# 780-00012-P3_rev2_Sch_M2_Focus_Drive.net
KiCad netlist of a schematic drawn in Altium Designer
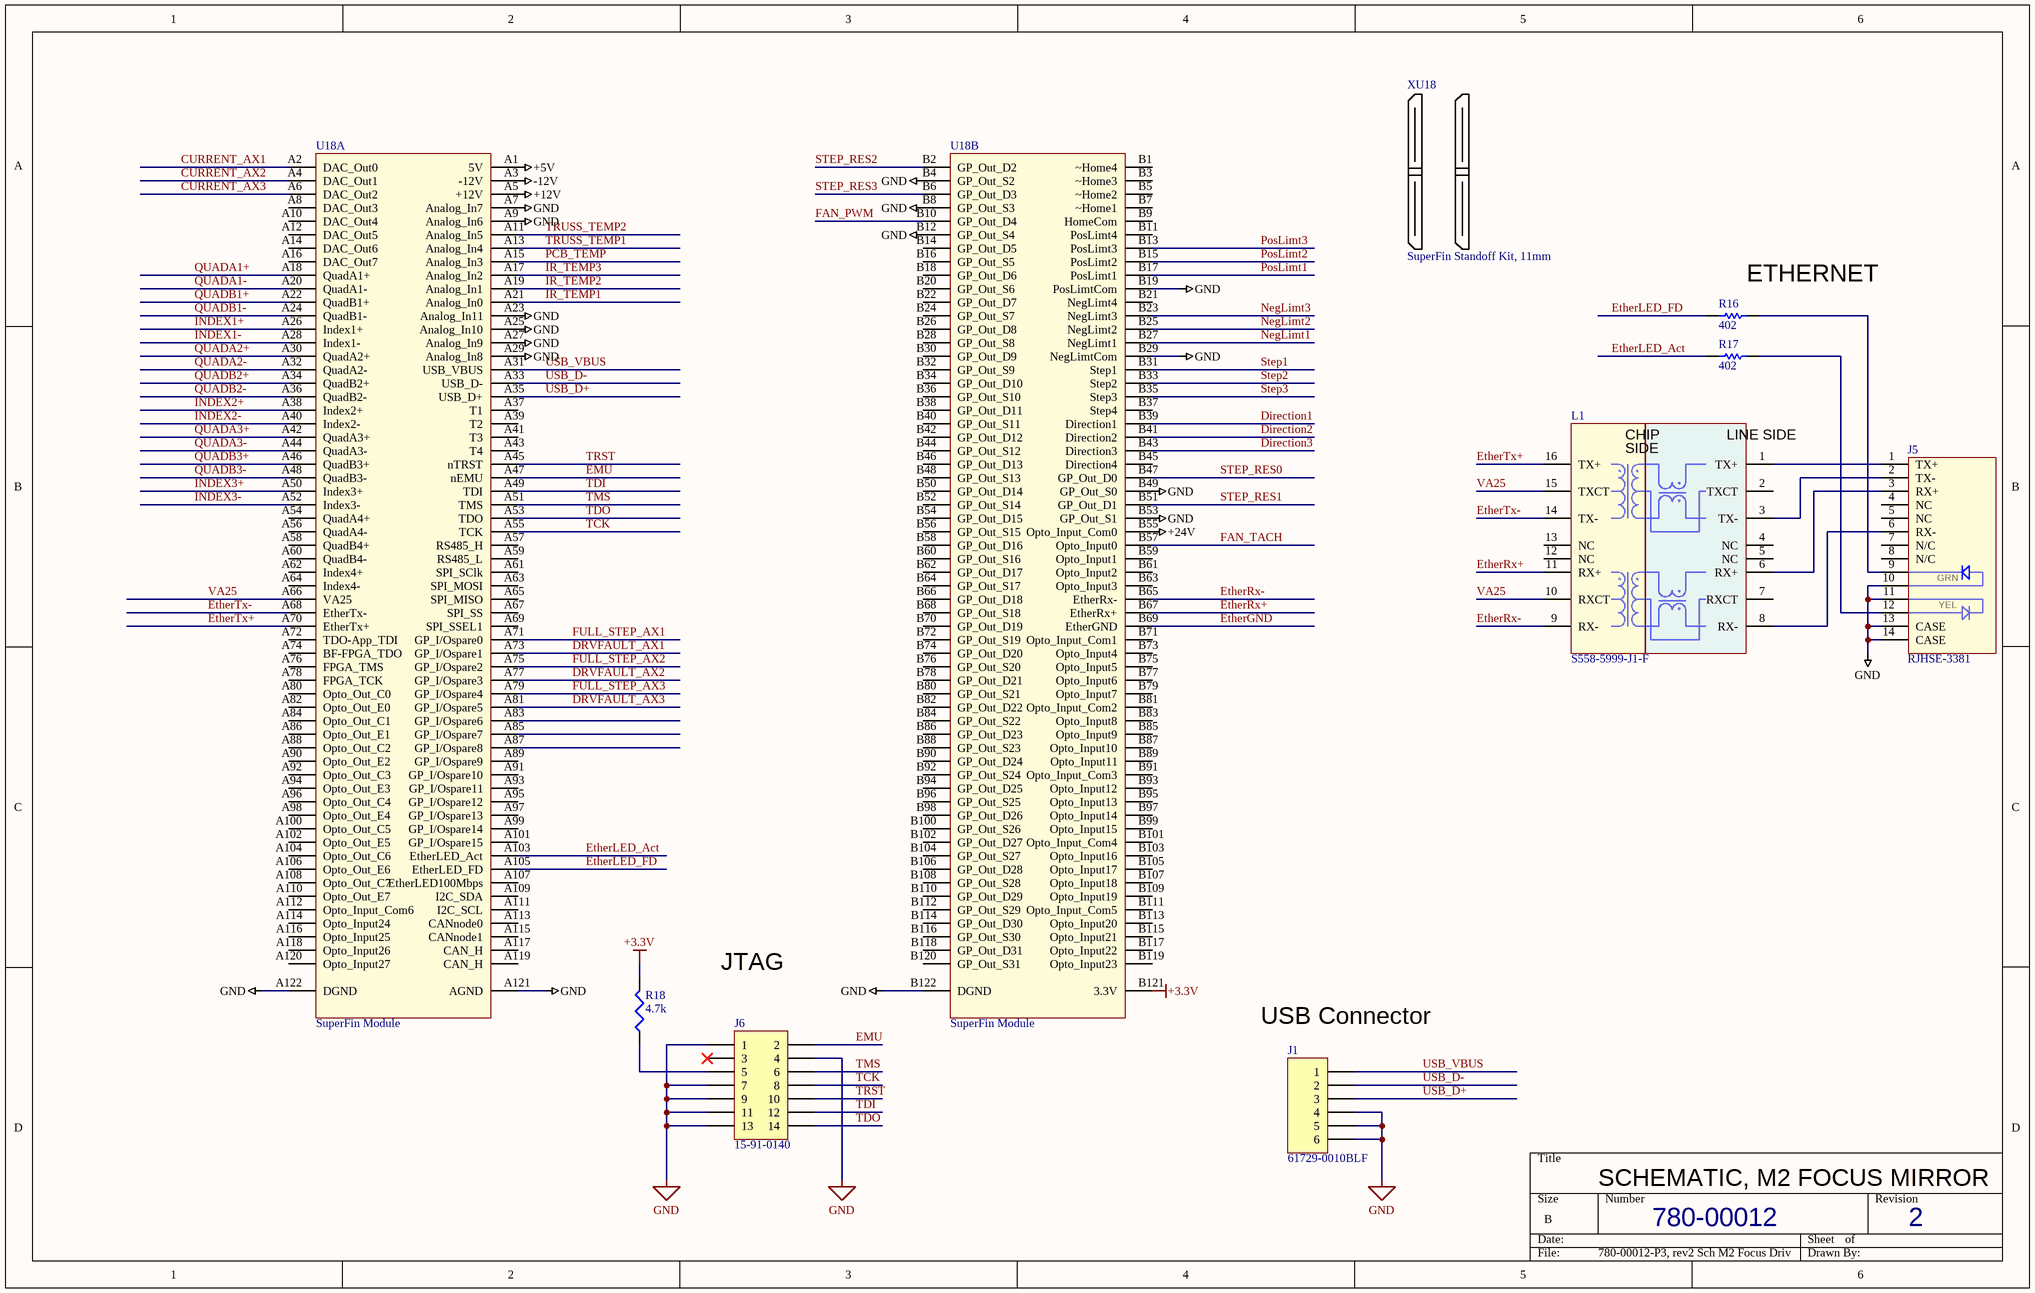
[diagram p0: 780-00012-P3, rev2 Sch M2 Focus Drive.SchDoc]

(export (version "E")
  (design (tool "Eeschema 10.0.6"))
  (components
    (comp (ref "J1")
      (value "61729-0010BLF")
      (footprint "USB Vertical PCB")
      (description "Header, 6-Pin")
      (fields (field (name "MANUFACTURER") "FCI"))
      (libsource (lib "Miscellaneous Connectors") (part "Header 6"))
    )
    (comp (ref "J5")
      (value "RJHSE-3381")
      (footprint "RJ45, VERT MOUNT, NO MAGNETICS")
      (description "Vertical PC mount, w/o magnetics")
      (libsource (lib "Richs Schematic Components") (part "CONN RJ-45 w/o magnetics"))
    )
    (comp (ref "J6")
      (value "15-91-0140")
      (footprint "HDR2X7")
      (description "Header, 7-Pin, Dual row")
      (fields (field (name "MANUFACTURER") "Molex/Waldom"))
      (libsource (lib "Miscellaneous Connectors") (part "Header 7X2"))
    )
    (comp (ref "L1")
      (value "S558-5999-J1-F")
      (footprint "10/100BT Magetics module")
      (description "10/100BT Magnetics Module")
      (libsource (lib "Richs Schematic Components") (part "Ethernet Magnetics module"))
    )
    (comp (ref "R16")
      (value "402")
      (footprint "SMD_0805")
      (description "Resistor 0805")
      (fields (field (name "MANUFACTURER") "Vishay/Dale") (field (name "Comment") "Res 0805"))
      (libsource (lib "Richs Schematic Components") (part "Res SMD"))
    )
    (comp (ref "R17")
      (value "402")
      (footprint "SMD_0805")
      (description "Resistor 0805")
      (fields (field (name "MANUFACTURER") "Vishay/Dale") (field (name "Comment") "Res 0805"))
      (libsource (lib "Richs Schematic Components") (part "Res SMD"))
    )
    (comp (ref "R18")
      (value "4.7k")
      (footprint "2012[0805]")
      (description "Resistor")
      (fields (field (name "MANUFACTURER") "Dale/Vishay"))
      (libsource (lib "Miscellaneous Devices") (part "Res3"))
    )
    (comp (ref "U18")
      (value "SuperFin Module")
      (footprint "SuperFin Footprint")
      (libsource (lib "Richs Schematic Components") (part "SuperFin Module"))
    )
    (comp (ref "XU18")
      (value "SuperFin Standoff Kit, 11mm")
      (libsource (lib "Richs Schematic Components") (part "SuperFin Standoff Kit, 11mm"))
    )
  )
  (nets
    (net (code "1") (name "+3.3V") (class "Default")
      (node (ref "R18") (pin "2") (pinfunction "2_2") (pintype "passive"))
      (node (ref "U18") (pin "B121") (pinfunction "3.3V_B121") (pintype "passive"))
    )
    (net (code "2") (name "+5V") (class "Default")
      (node (ref "U18") (pin "A1") (pinfunction "5V_A1") (pintype "passive"))
    )
    (net (code "3") (name "+12V") (class "Default")
      (node (ref "U18") (pin "A5") (pinfunction "+12V_A5") (pintype "passive"))
    )
    (net (code "4") (name "+24V") (class "Default")
      (node (ref "U18") (pin "B55") (pinfunction "Opto_Input_Com0_B55") (pintype "passive"))
    )
    (net (code "5") (name "-12V") (class "Default")
      (node (ref "U18") (pin "A3") (pinfunction "-12V_A3") (pintype "passive"))
    )
    (net (code "6") (name "/CURRENT_AX1") (class "Default")
      (node (ref "U18") (pin "A2") (pinfunction "DAC_Out0_A2") (pintype "passive"))
    )
    (net (code "7") (name "/CURRENT_AX2") (class "Default")
      (node (ref "U18") (pin "A4") (pinfunction "DAC_Out1_A4") (pintype "passive"))
    )
    (net (code "8") (name "/CURRENT_AX3") (class "Default")
      (node (ref "U18") (pin "A6") (pinfunction "DAC_Out2_A6") (pintype "passive"))
    )
    (net (code "9") (name "/DRVFAULT_AX1") (class "Default")
      (node (ref "U18") (pin "A73") (pinfunction "GP_I/Ospare1_A73") (pintype "passive"))
    )
    (net (code "10") (name "/DRVFAULT_AX2") (class "Default")
      (node (ref "U18") (pin "A77") (pinfunction "GP_I/Ospare3_A77") (pintype "passive"))
    )
    (net (code "11") (name "/DRVFAULT_AX3") (class "Default")
      (node (ref "U18") (pin "A81") (pinfunction "GP_I/Ospare5_A81") (pintype "passive"))
    )
    (net (code "12") (name "/Direction1") (class "Default")
      (node (ref "U18") (pin "B39") (pinfunction "Direction1_B39") (pintype "passive"))
    )
    (net (code "13") (name "/Direction2") (class "Default")
      (node (ref "U18") (pin "B41") (pinfunction "Direction2_B41") (pintype "passive"))
    )
    (net (code "14") (name "/Direction3") (class "Default")
      (node (ref "U18") (pin "B43") (pinfunction "Direction3_B43") (pintype "passive"))
    )
    (net (code "15") (name "/EMU") (class "Default")
      (node (ref "J6") (pin "2") (pinfunction "2_2") (pintype "passive"))
      (node (ref "U18") (pin "A47") (pinfunction "nEMU_A47") (pintype "passive"))
    )
    (net (code "16") (name "/EtherGND") (class "Default")
      (node (ref "U18") (pin "B69") (pinfunction "EtherGND_B69") (pintype "passive"))
    )
    (net (code "17") (name "/EtherLED_Act") (class "Default")
      (node (ref "R17") (pin "1") (pinfunction "1_1") (pintype "passive"))
      (node (ref "U18") (pin "A103") (pinfunction "EtherLED_Act_A103") (pintype "passive"))
    )
    (net (code "18") (name "/EtherLED_FD") (class "Default")
      (node (ref "R16") (pin "1") (pinfunction "1_1") (pintype "passive"))
      (node (ref "U18") (pin "A105") (pinfunction "EtherLED_FD_A105") (pintype "passive"))
    )
    (net (code "19") (name "/EtherRx+") (class "Default")
      (node (ref "L1") (pin "11") (pinfunction "RX+_11") (pintype "passive"))
      (node (ref "U18") (pin "B67") (pinfunction "EtherRx+_B67") (pintype "passive"))
    )
    (net (code "20") (name "/EtherRx-") (class "Default")
      (node (ref "L1") (pin "9") (pinfunction "RX-_9") (pintype "passive"))
      (node (ref "U18") (pin "B65") (pinfunction "EtherRx-_B65") (pintype "passive"))
    )
    (net (code "21") (name "/EtherTx+") (class "Default")
      (node (ref "L1") (pin "16") (pinfunction "TX+_16") (pintype "passive"))
      (node (ref "U18") (pin "A70") (pinfunction "EtherTx+_A70") (pintype "passive"))
    )
    (net (code "22") (name "/EtherTx-") (class "Default")
      (node (ref "L1") (pin "14") (pinfunction "TX-_14") (pintype "passive"))
      (node (ref "U18") (pin "A68") (pinfunction "EtherTx-_A68") (pintype "passive"))
    )
    (net (code "23") (name "/FAN_PWM") (class "Default")
      (node (ref "U18") (pin "B10") (pinfunction "GP_Out_D4_B10") (pintype "passive"))
    )
    (net (code "24") (name "/FAN_TACH") (class "Default")
      (node (ref "U18") (pin "B57") (pinfunction "Opto_Input0_B57") (pintype "passive"))
    )
    (net (code "25") (name "/FULL_STEP_AX1") (class "Default")
      (node (ref "U18") (pin "A71") (pinfunction "GP_I/Ospare0_A71") (pintype "passive"))
    )
    (net (code "26") (name "/FULL_STEP_AX2") (class "Default")
      (node (ref "U18") (pin "A75") (pinfunction "GP_I/Ospare2_A75") (pintype "passive"))
    )
    (net (code "27") (name "/FULL_STEP_AX3") (class "Default")
      (node (ref "U18") (pin "A79") (pinfunction "GP_I/Ospare4_A79") (pintype "passive"))
    )
    (net (code "28") (name "/INDEX1+") (class "Default")
      (node (ref "U18") (pin "A26") (pinfunction "Index1+_A26") (pintype "passive"))
    )
    (net (code "29") (name "/INDEX1-") (class "Default")
      (node (ref "U18") (pin "A28") (pinfunction "Index1-_A28") (pintype "passive"))
    )
    (net (code "30") (name "/INDEX2+") (class "Default")
      (node (ref "U18") (pin "A38") (pinfunction "Index2+_A38") (pintype "passive"))
    )
    (net (code "31") (name "/INDEX2-") (class "Default")
      (node (ref "U18") (pin "A40") (pinfunction "Index2-_A40") (pintype "passive"))
    )
    (net (code "32") (name "/INDEX3+") (class "Default")
      (node (ref "U18") (pin "A50") (pinfunction "Index3+_A50") (pintype "passive"))
    )
    (net (code "33") (name "/INDEX3-") (class "Default")
      (node (ref "U18") (pin "A52") (pinfunction "Index3-_A52") (pintype "passive"))
    )
    (net (code "34") (name "/IR_TEMP1") (class "Default")
      (node (ref "U18") (pin "A21") (pinfunction "Analog_In0_A21") (pintype "passive"))
    )
    (net (code "35") (name "/IR_TEMP2") (class "Default")
      (node (ref "U18") (pin "A19") (pinfunction "Analog_In1_A19") (pintype "passive"))
    )
    (net (code "36") (name "/IR_TEMP3") (class "Default")
      (node (ref "U18") (pin "A17") (pinfunction "Analog_In2_A17") (pintype "passive"))
    )
    (net (code "37") (name "/NegLimt1") (class "Default")
      (node (ref "U18") (pin "B27") (pinfunction "NegLimt1_B27") (pintype "passive"))
    )
    (net (code "38") (name "/NegLimt2") (class "Default")
      (node (ref "U18") (pin "B25") (pinfunction "NegLimt2_B25") (pintype "passive"))
    )
    (net (code "39") (name "/NegLimt3") (class "Default")
      (node (ref "U18") (pin "B23") (pinfunction "NegLimt3_B23") (pintype "passive"))
    )
    (net (code "40") (name "/PCB_TEMP") (class "Default")
      (node (ref "U18") (pin "A15") (pinfunction "Analog_In3_A15") (pintype "passive"))
    )
    (net (code "41") (name "/PosLimt1") (class "Default")
      (node (ref "U18") (pin "B17") (pinfunction "PosLimt1_B17") (pintype "passive"))
    )
    (net (code "42") (name "/PosLimt2") (class "Default")
      (node (ref "U18") (pin "B15") (pinfunction "PosLimt2_B15") (pintype "passive"))
    )
    (net (code "43") (name "/PosLimt3") (class "Default")
      (node (ref "U18") (pin "B13") (pinfunction "PosLimt3_B13") (pintype "passive"))
    )
    (net (code "44") (name "/QUADA1+") (class "Default")
      (node (ref "U18") (pin "A18") (pinfunction "QuadA1+_A18") (pintype "passive"))
    )
    (net (code "45") (name "/QUADA1-") (class "Default")
      (node (ref "U18") (pin "A20") (pinfunction "QuadA1-_A20") (pintype "passive"))
    )
    (net (code "46") (name "/QUADA2+") (class "Default")
      (node (ref "U18") (pin "A30") (pinfunction "QuadA2+_A30") (pintype "passive"))
    )
    (net (code "47") (name "/QUADA2-") (class "Default")
      (node (ref "U18") (pin "A32") (pinfunction "QuadA2-_A32") (pintype "passive"))
    )
    (net (code "48") (name "/QUADA3+") (class "Default")
      (node (ref "U18") (pin "A42") (pinfunction "QuadA3+_A42") (pintype "passive"))
    )
    (net (code "49") (name "/QUADA3-") (class "Default")
      (node (ref "U18") (pin "A44") (pinfunction "QuadA3-_A44") (pintype "passive"))
    )
    (net (code "50") (name "/QUADB1+") (class "Default")
      (node (ref "U18") (pin "A22") (pinfunction "QuadB1+_A22") (pintype "passive"))
    )
    (net (code "51") (name "/QUADB1-") (class "Default")
      (node (ref "U18") (pin "A24") (pinfunction "QuadB1-_A24") (pintype "passive"))
    )
    (net (code "52") (name "/QUADB2+") (class "Default")
      (node (ref "U18") (pin "A34") (pinfunction "QuadB2+_A34") (pintype "passive"))
    )
    (net (code "53") (name "/QUADB2-") (class "Default")
      (node (ref "U18") (pin "A36") (pinfunction "QuadB2-_A36") (pintype "passive"))
    )
    (net (code "54") (name "/QUADB3+") (class "Default")
      (node (ref "U18") (pin "A46") (pinfunction "QuadB3+_A46") (pintype "passive"))
    )
    (net (code "55") (name "/QUADB3-") (class "Default")
      (node (ref "U18") (pin "A48") (pinfunction "QuadB3-_A48") (pintype "passive"))
    )
    (net (code "56") (name "/STEP_RES0") (class "Default")
      (node (ref "U18") (pin "B47") (pinfunction "GP_Out_D0_B47") (pintype "passive"))
    )
    (net (code "57") (name "/STEP_RES1") (class "Default")
      (node (ref "U18") (pin "B51") (pinfunction "GP_Out_D1_B51") (pintype "passive"))
    )
    (net (code "58") (name "/STEP_RES2") (class "Default")
      (node (ref "U18") (pin "B2") (pinfunction "GP_Out_D2_B2") (pintype "passive"))
    )
    (net (code "59") (name "/STEP_RES3") (class "Default")
      (node (ref "U18") (pin "B6") (pinfunction "GP_Out_D3_B6") (pintype "passive"))
    )
    (net (code "60") (name "/Step1") (class "Default")
      (node (ref "U18") (pin "B31") (pinfunction "Step1_B31") (pintype "passive"))
    )
    (net (code "61") (name "/Step2") (class "Default")
      (node (ref "U18") (pin "B33") (pinfunction "Step2_B33") (pintype "passive"))
    )
    (net (code "62") (name "/Step3") (class "Default")
      (node (ref "U18") (pin "B35") (pinfunction "Step3_B35") (pintype "passive"))
    )
    (net (code "63") (name "/TCK") (class "Default")
      (node (ref "J6") (pin "8") (pinfunction "8_8") (pintype "passive"))
      (node (ref "U18") (pin "A55") (pinfunction "TCK_A55") (pintype "passive"))
    )
    (net (code "64") (name "/TDI") (class "Default")
      (node (ref "J6") (pin "12") (pinfunction "12_12") (pintype "passive"))
      (node (ref "U18") (pin "A49") (pinfunction "TDI_A49") (pintype "passive"))
    )
    (net (code "65") (name "/TDO") (class "Default")
      (node (ref "J6") (pin "14") (pinfunction "14_14") (pintype "passive"))
      (node (ref "U18") (pin "A53") (pinfunction "TDO_A53") (pintype "passive"))
    )
    (net (code "66") (name "/TMS") (class "Default")
      (node (ref "J6") (pin "6") (pinfunction "6_6") (pintype "passive"))
      (node (ref "U18") (pin "A51") (pinfunction "TMS_A51") (pintype "passive"))
    )
    (net (code "67") (name "/TRST") (class "Default")
      (node (ref "J6") (pin "10") (pinfunction "10_10") (pintype "passive"))
      (node (ref "U18") (pin "A45") (pinfunction "nTRST_A45") (pintype "passive"))
    )
    (net (code "68") (name "/TRUSS_TEMP1") (class "Default")
      (node (ref "U18") (pin "A13") (pinfunction "Analog_In4_A13") (pintype "passive"))
    )
    (net (code "69") (name "/TRUSS_TEMP2") (class "Default")
      (node (ref "U18") (pin "A11") (pinfunction "Analog_In5_A11") (pintype "passive"))
    )
    (net (code "70") (name "/USB_D+") (class "Default")
      (node (ref "J1") (pin "3") (pinfunction "3_3") (pintype "passive"))
      (node (ref "U18") (pin "A35") (pinfunction "USB_D+_A35") (pintype "passive"))
    )
    (net (code "71") (name "/USB_D-") (class "Default")
      (node (ref "J1") (pin "2") (pinfunction "2_2") (pintype "passive"))
      (node (ref "U18") (pin "A33") (pinfunction "USB_D-_A33") (pintype "passive"))
    )
    (net (code "72") (name "/USB_VBUS") (class "Default")
      (node (ref "J1") (pin "1") (pinfunction "1_1") (pintype "passive"))
      (node (ref "U18") (pin "A31") (pinfunction "USB_VBUS_A31") (pintype "passive"))
    )
    (net (code "73") (name "/VA25") (class "Default")
      (node (ref "L1") (pin "10") (pinfunction "RXCT_10") (pintype "passive"))
      (node (ref "L1") (pin "15") (pinfunction "TXCT_15") (pintype "passive"))
      (node (ref "U18") (pin "A66") (pinfunction "VA25_A66") (pintype "passive"))
    )
    (net (code "74") (name "GND") (class "Default")
      (node (ref "J1") (pin "4") (pinfunction "4_4") (pintype "passive"))
      (node (ref "J1") (pin "5") (pinfunction "5_5") (pintype "passive"))
      (node (ref "J1") (pin "6") (pinfunction "6_6") (pintype "passive"))
      (node (ref "J5") (pin "10") (pinfunction "GRN-Cathode_10") (pintype "passive"))
      (node (ref "J5") (pin "11") (pinfunction "YEL-Cathode_11") (pintype "passive"))
      (node (ref "J5") (pin "13") (pinfunction "CASE_13") (pintype "passive"))
      (node (ref "J5") (pin "14") (pinfunction "CASE_14") (pintype "passive"))
      (node (ref "J6") (pin "1") (pinfunction "1_1") (pintype "passive"))
      (node (ref "J6") (pin "11") (pinfunction "11_11") (pintype "passive"))
      (node (ref "J6") (pin "13") (pinfunction "13_13") (pintype "passive"))
      (node (ref "J6") (pin "4") (pinfunction "4_4") (pintype "passive"))
      (node (ref "J6") (pin "7") (pinfunction "7_7") (pintype "passive"))
      (node (ref "J6") (pin "9") (pinfunction "9_9") (pintype "passive"))
      (node (ref "U18") (pin "A121") (pinfunction "AGND_A121") (pintype "passive"))
      (node (ref "U18") (pin "A122") (pinfunction "DGND_A122") (pintype "passive"))
      (node (ref "U18") (pin "A23") (pinfunction "Analog_In11_A23") (pintype "passive"))
      (node (ref "U18") (pin "A25") (pinfunction "Analog_In10_A25") (pintype "passive"))
      (node (ref "U18") (pin "A27") (pinfunction "Analog_In9_A27") (pintype "passive"))
      (node (ref "U18") (pin "A29") (pinfunction "Analog_In8_A29") (pintype "passive"))
      (node (ref "U18") (pin "A7") (pinfunction "Analog_In7_A7") (pintype "passive"))
      (node (ref "U18") (pin "A9") (pinfunction "Analog_In6_A9") (pintype "passive"))
      (node (ref "U18") (pin "B12") (pinfunction "GP_Out_S4_B12") (pintype "passive"))
      (node (ref "U18") (pin "B122") (pinfunction "DGND_B122") (pintype "passive"))
      (node (ref "U18") (pin "B19") (pinfunction "PosLimtCom_B19") (pintype "passive"))
      (node (ref "U18") (pin "B29") (pinfunction "NegLimtCom_B29") (pintype "passive"))
      (node (ref "U18") (pin "B4") (pinfunction "GP_Out_S2_B4") (pintype "passive"))
      (node (ref "U18") (pin "B49") (pinfunction "GP_Out_S0_B49") (pintype "passive"))
      (node (ref "U18") (pin "B53") (pinfunction "GP_Out_S1_B53") (pintype "passive"))
      (node (ref "U18") (pin "B8") (pinfunction "GP_Out_S3_B8") (pintype "passive"))
    )
    (net (code "75") (name "Net-(J5-GRN-Anode)") (class "Default")
      (node (ref "J5") (pin "9") (pinfunction "GRN-Anode_9") (pintype "passive"))
      (node (ref "R16") (pin "2") (pinfunction "2_2") (pintype "passive"))
    )
    (net (code "76") (name "Net-(J5-RX+)") (class "Default")
      (node (ref "J5") (pin "3") (pinfunction "RX+_3") (pintype "passive"))
      (node (ref "L1") (pin "6") (pinfunction "RX+_6") (pintype "passive"))
    )
    (net (code "77") (name "Net-(J5-RX-)") (class "Default")
      (node (ref "J5") (pin "6") (pinfunction "RX-_6") (pintype "passive"))
      (node (ref "L1") (pin "8") (pinfunction "RX-_8") (pintype "passive"))
    )
    (net (code "78") (name "Net-(J5-TX+)") (class "Default")
      (node (ref "J5") (pin "1") (pinfunction "TX+_1") (pintype "passive"))
      (node (ref "L1") (pin "1") (pinfunction "TX+_1") (pintype "passive"))
    )
    (net (code "79") (name "Net-(J5-TX-)") (class "Default")
      (node (ref "J5") (pin "2") (pinfunction "TX-_2") (pintype "passive"))
      (node (ref "L1") (pin "3") (pinfunction "TX-_3") (pintype "passive"))
    )
    (net (code "80") (name "Net-(J5-YEL-Anode)") (class "Default")
      (node (ref "J5") (pin "12") (pinfunction "YEL-Anode_12") (pintype "passive"))
      (node (ref "R17") (pin "2") (pinfunction "2_2") (pintype "passive"))
    )
    (net (code "81") (name "Net-(J6-Pad5)") (class "Default")
      (node (ref "J6") (pin "5") (pinfunction "5_5") (pintype "passive"))
      (node (ref "R18") (pin "1") (pinfunction "1_1") (pintype "passive"))
    )
    (net (code "82") (name "unconnected-(J5-NC-Pad4)") (class "Default")
      (node (ref "J5") (pin "4") (pinfunction "NC_4") (pintype "passive"))
    )
    (net (code "83") (name "unconnected-(J5-NC-Pad5)") (class "Default")
      (node (ref "J5") (pin "5") (pinfunction "NC_5") (pintype "passive"))
    )
    (net (code "84") (name "unconnected-(J5-N{slash}C-Pad7)") (class "Default")
      (node (ref "J5") (pin "7") (pinfunction "N/C_7") (pintype "passive"))
    )
    (net (code "85") (name "unconnected-(J5-N{slash}C-Pad8)") (class "Default")
      (node (ref "J5") (pin "8") (pinfunction "N/C_8") (pintype "passive"))
    )
    (net (code "86") (name "unconnected-(J6-Pad3)") (class "Default")
      (node (ref "J6") (pin "3") (pinfunction "3_3") (pintype "passive+no_connect"))
    )
    (net (code "87") (name "unconnected-(L1-NC-Pad4)") (class "Default")
      (node (ref "L1") (pin "4") (pinfunction "NC_4") (pintype "passive"))
    )
    (net (code "88") (name "unconnected-(L1-NC-Pad5)") (class "Default")
      (node (ref "L1") (pin "5") (pinfunction "NC_5") (pintype "passive"))
    )
    (net (code "89") (name "unconnected-(L1-NC-Pad12)") (class "Default")
      (node (ref "L1") (pin "12") (pinfunction "NC_12") (pintype "passive"))
    )
    (net (code "90") (name "unconnected-(L1-NC-Pad13)") (class "Default")
      (node (ref "L1") (pin "13") (pinfunction "NC_13") (pintype "passive"))
    )
    (net (code "91") (name "unconnected-(L1-RXCT-Pad7)") (class "Default")
      (node (ref "L1") (pin "7") (pinfunction "RXCT_7") (pintype "passive"))
    )
    (net (code "92") (name "unconnected-(L1-TXCT-Pad2)") (class "Default")
      (node (ref "L1") (pin "2") (pinfunction "TXCT_2") (pintype "passive"))
    )
    (net (code "93") (name "unconnected-(U18A-BF-FPGA_TDO-PadA74)") (class "Default")
      (node (ref "U18") (pin "A74") (pinfunction "BF-FPGA_TDO_A74") (pintype "passive"))
    )
    (net (code "94") (name "unconnected-(U18A-CAN_H-PadA117)") (class "Default")
      (node (ref "U18") (pin "A117") (pinfunction "CAN_H_A117") (pintype "passive"))
    )
    (net (code "95") (name "unconnected-(U18A-CAN_H-PadA119)") (class "Default")
      (node (ref "U18") (pin "A119") (pinfunction "CAN_H_A119") (pintype "passive"))
    )
    (net (code "96") (name "unconnected-(U18A-CANnode0-PadA113)") (class "Default")
      (node (ref "U18") (pin "A113") (pinfunction "CANnode0_A113") (pintype "passive"))
    )
    (net (code "97") (name "unconnected-(U18A-CANnode1-PadA115)") (class "Default")
      (node (ref "U18") (pin "A115") (pinfunction "CANnode1_A115") (pintype "passive"))
    )
    (net (code "98") (name "unconnected-(U18A-DAC_Out3-PadA8)") (class "Default")
      (node (ref "U18") (pin "A8") (pinfunction "DAC_Out3_A8") (pintype "passive"))
    )
    (net (code "99") (name "unconnected-(U18A-DAC_Out4-PadA10)") (class "Default")
      (node (ref "U18") (pin "A10") (pinfunction "DAC_Out4_A10") (pintype "passive"))
    )
    (net (code "100") (name "unconnected-(U18A-DAC_Out5-PadA12)") (class "Default")
      (node (ref "U18") (pin "A12") (pinfunction "DAC_Out5_A12") (pintype "passive"))
    )
    (net (code "101") (name "unconnected-(U18A-DAC_Out6-PadA14)") (class "Default")
      (node (ref "U18") (pin "A14") (pinfunction "DAC_Out6_A14") (pintype "passive"))
    )
    (net (code "102") (name "unconnected-(U18A-DAC_Out7-PadA16)") (class "Default")
      (node (ref "U18") (pin "A16") (pinfunction "DAC_Out7_A16") (pintype "passive"))
    )
    (net (code "103") (name "unconnected-(U18A-EtherLED100Mbps-PadA107)") (class "Default")
      (node (ref "U18") (pin "A107") (pinfunction "EtherLED100Mbps_A107") (pintype "passive"))
    )
    (net (code "104") (name "unconnected-(U18A-FPGA_TCK-PadA78)") (class "Default")
      (node (ref "U18") (pin "A78") (pinfunction "FPGA_TCK_A78") (pintype "passive"))
    )
    (net (code "105") (name "unconnected-(U18A-FPGA_TMS-PadA76)") (class "Default")
      (node (ref "U18") (pin "A76") (pinfunction "FPGA_TMS_A76") (pintype "passive"))
    )
    (net (code "106") (name "unconnected-(U18A-GP_I{slash}Ospare6-PadA83)") (class "Default")
      (node (ref "U18") (pin "A83") (pinfunction "GP_I/Ospare6_A83") (pintype "passive"))
    )
    (net (code "107") (name "unconnected-(U18A-GP_I{slash}Ospare7-PadA85)") (class "Default")
      (node (ref "U18") (pin "A85") (pinfunction "GP_I/Ospare7_A85") (pintype "passive"))
    )
    (net (code "108") (name "unconnected-(U18A-GP_I{slash}Ospare8-PadA87)") (class "Default")
      (node (ref "U18") (pin "A87") (pinfunction "GP_I/Ospare8_A87") (pintype "passive"))
    )
    (net (code "109") (name "unconnected-(U18A-GP_I{slash}Ospare9-PadA89)") (class "Default")
      (node (ref "U18") (pin "A89") (pinfunction "GP_I/Ospare9_A89") (pintype "passive"))
    )
    (net (code "110") (name "unconnected-(U18A-GP_I{slash}Ospare10-PadA91)") (class "Default")
      (node (ref "U18") (pin "A91") (pinfunction "GP_I/Ospare10_A91") (pintype "passive"))
    )
    (net (code "111") (name "unconnected-(U18A-GP_I{slash}Ospare11-PadA93)") (class "Default")
      (node (ref "U18") (pin "A93") (pinfunction "GP_I/Ospare11_A93") (pintype "passive"))
    )
    (net (code "112") (name "unconnected-(U18A-GP_I{slash}Ospare12-PadA95)") (class "Default")
      (node (ref "U18") (pin "A95") (pinfunction "GP_I/Ospare12_A95") (pintype "passive"))
    )
    (net (code "113") (name "unconnected-(U18A-GP_I{slash}Ospare13-PadA97)") (class "Default")
      (node (ref "U18") (pin "A97") (pinfunction "GP_I/Ospare13_A97") (pintype "passive"))
    )
    (net (code "114") (name "unconnected-(U18A-GP_I{slash}Ospare14-PadA99)") (class "Default")
      (node (ref "U18") (pin "A99") (pinfunction "GP_I/Ospare14_A99") (pintype "passive"))
    )
    (net (code "115") (name "unconnected-(U18A-GP_I{slash}Ospare15-PadA101)") (class "Default")
      (node (ref "U18") (pin "A101") (pinfunction "GP_I/Ospare15_A101") (pintype "passive"))
    )
    (net (code "116") (name "unconnected-(U18A-I2C_SCL-PadA111)") (class "Default")
      (node (ref "U18") (pin "A111") (pinfunction "I2C_SCL_A111") (pintype "passive"))
    )
    (net (code "117") (name "unconnected-(U18A-I2C_SDA-PadA109)") (class "Default")
      (node (ref "U18") (pin "A109") (pinfunction "I2C_SDA_A109") (pintype "passive"))
    )
    (net (code "118") (name "unconnected-(U18A-Index4+-PadA62)") (class "Default")
      (node (ref "U18") (pin "A62") (pinfunction "Index4+_A62") (pintype "passive"))
    )
    (net (code "119") (name "unconnected-(U18A-Index4--PadA64)") (class "Default")
      (node (ref "U18") (pin "A64") (pinfunction "Index4-_A64") (pintype "passive"))
    )
    (net (code "120") (name "unconnected-(U18A-Opto_Input24-PadA114)") (class "Default")
      (node (ref "U18") (pin "A114") (pinfunction "Opto_Input24_A114") (pintype "passive"))
    )
    (net (code "121") (name "unconnected-(U18A-Opto_Input25-PadA116)") (class "Default")
      (node (ref "U18") (pin "A116") (pinfunction "Opto_Input25_A116") (pintype "passive"))
    )
    (net (code "122") (name "unconnected-(U18A-Opto_Input26-PadA118)") (class "Default")
      (node (ref "U18") (pin "A118") (pinfunction "Opto_Input26_A118") (pintype "passive"))
    )
    (net (code "123") (name "unconnected-(U18A-Opto_Input27-PadA120)") (class "Default")
      (node (ref "U18") (pin "A120") (pinfunction "Opto_Input27_A120") (pintype "passive"))
    )
    (net (code "124") (name "unconnected-(U18A-Opto_Input_Com6-PadA112)") (class "Default")
      (node (ref "U18") (pin "A112") (pinfunction "Opto_Input_Com6_A112") (pintype "passive"))
    )
    (net (code "125") (name "unconnected-(U18A-Opto_Out_C0-PadA80)") (class "Default")
      (node (ref "U18") (pin "A80") (pinfunction "Opto_Out_C0_A80") (pintype "passive"))
    )
    (net (code "126") (name "unconnected-(U18A-Opto_Out_C1-PadA84)") (class "Default")
      (node (ref "U18") (pin "A84") (pinfunction "Opto_Out_C1_A84") (pintype "passive"))
    )
    (net (code "127") (name "unconnected-(U18A-Opto_Out_C2-PadA88)") (class "Default")
      (node (ref "U18") (pin "A88") (pinfunction "Opto_Out_C2_A88") (pintype "passive"))
    )
    (net (code "128") (name "unconnected-(U18A-Opto_Out_C3-PadA92)") (class "Default")
      (node (ref "U18") (pin "A92") (pinfunction "Opto_Out_C3_A92") (pintype "passive"))
    )
    (net (code "129") (name "unconnected-(U18A-Opto_Out_C4-PadA96)") (class "Default")
      (node (ref "U18") (pin "A96") (pinfunction "Opto_Out_C4_A96") (pintype "passive"))
    )
    (net (code "130") (name "unconnected-(U18A-Opto_Out_C5-PadA100)") (class "Default")
      (node (ref "U18") (pin "A100") (pinfunction "Opto_Out_C5_A100") (pintype "passive"))
    )
    (net (code "131") (name "unconnected-(U18A-Opto_Out_C6-PadA104)") (class "Default")
      (node (ref "U18") (pin "A104") (pinfunction "Opto_Out_C6_A104") (pintype "passive"))
    )
    (net (code "132") (name "unconnected-(U18A-Opto_Out_C7-PadA108)") (class "Default")
      (node (ref "U18") (pin "A108") (pinfunction "Opto_Out_C7_A108") (pintype "passive"))
    )
    (net (code "133") (name "unconnected-(U18A-Opto_Out_E0-PadA82)") (class "Default")
      (node (ref "U18") (pin "A82") (pinfunction "Opto_Out_E0_A82") (pintype "passive"))
    )
    (net (code "134") (name "unconnected-(U18A-Opto_Out_E1-PadA86)") (class "Default")
      (node (ref "U18") (pin "A86") (pinfunction "Opto_Out_E1_A86") (pintype "passive"))
    )
    (net (code "135") (name "unconnected-(U18A-Opto_Out_E2-PadA90)") (class "Default")
      (node (ref "U18") (pin "A90") (pinfunction "Opto_Out_E2_A90") (pintype "passive"))
    )
    (net (code "136") (name "unconnected-(U18A-Opto_Out_E3-PadA94)") (class "Default")
      (node (ref "U18") (pin "A94") (pinfunction "Opto_Out_E3_A94") (pintype "passive"))
    )
    (net (code "137") (name "unconnected-(U18A-Opto_Out_E4-PadA98)") (class "Default")
      (node (ref "U18") (pin "A98") (pinfunction "Opto_Out_E4_A98") (pintype "passive"))
    )
    (net (code "138") (name "unconnected-(U18A-Opto_Out_E5-PadA102)") (class "Default")
      (node (ref "U18") (pin "A102") (pinfunction "Opto_Out_E5_A102") (pintype "passive"))
    )
    (net (code "139") (name "unconnected-(U18A-Opto_Out_E6-PadA106)") (class "Default")
      (node (ref "U18") (pin "A106") (pinfunction "Opto_Out_E6_A106") (pintype "passive"))
    )
    (net (code "140") (name "unconnected-(U18A-Opto_Out_E7-PadA110)") (class "Default")
      (node (ref "U18") (pin "A110") (pinfunction "Opto_Out_E7_A110") (pintype "passive"))
    )
    (net (code "141") (name "unconnected-(U18A-QuadA4+-PadA54)") (class "Default")
      (node (ref "U18") (pin "A54") (pinfunction "QuadA4+_A54") (pintype "passive"))
    )
    (net (code "142") (name "unconnected-(U18A-QuadA4--PadA56)") (class "Default")
      (node (ref "U18") (pin "A56") (pinfunction "QuadA4-_A56") (pintype "passive"))
    )
    (net (code "143") (name "unconnected-(U18A-QuadB4+-PadA58)") (class "Default")
      (node (ref "U18") (pin "A58") (pinfunction "QuadB4+_A58") (pintype "passive"))
    )
    (net (code "144") (name "unconnected-(U18A-QuadB4--PadA60)") (class "Default")
      (node (ref "U18") (pin "A60") (pinfunction "QuadB4-_A60") (pintype "passive"))
    )
    (net (code "145") (name "unconnected-(U18A-RS485_H-PadA57)") (class "Default")
      (node (ref "U18") (pin "A57") (pinfunction "RS485_H_A57") (pintype "passive"))
    )
    (net (code "146") (name "unconnected-(U18A-RS485_L-PadA59)") (class "Default")
      (node (ref "U18") (pin "A59") (pinfunction "RS485_L_A59") (pintype "passive"))
    )
    (net (code "147") (name "unconnected-(U18A-SPI_MISO-PadA65)") (class "Default")
      (node (ref "U18") (pin "A65") (pinfunction "SPI_MISO_A65") (pintype "passive"))
    )
    (net (code "148") (name "unconnected-(U18A-SPI_MOSI-PadA63)") (class "Default")
      (node (ref "U18") (pin "A63") (pinfunction "SPI_MOSI_A63") (pintype "passive"))
    )
    (net (code "149") (name "unconnected-(U18A-SPI_SClk-PadA61)") (class "Default")
      (node (ref "U18") (pin "A61") (pinfunction "SPI_SClk_A61") (pintype "passive"))
    )
    (net (code "150") (name "unconnected-(U18A-SPI_SS-PadA67)") (class "Default")
      (node (ref "U18") (pin "A67") (pinfunction "SPI_SS_A67") (pintype "passive"))
    )
    (net (code "151") (name "unconnected-(U18A-SPI_SSEL1-PadA69)") (class "Default")
      (node (ref "U18") (pin "A69") (pinfunction "SPI_SSEL1_A69") (pintype "passive"))
    )
    (net (code "152") (name "unconnected-(U18A-T1-PadA37)") (class "Default")
      (node (ref "U18") (pin "A37") (pinfunction "T1_A37") (pintype "passive"))
    )
    (net (code "153") (name "unconnected-(U18A-T2-PadA39)") (class "Default")
      (node (ref "U18") (pin "A39") (pinfunction "T2_A39") (pintype "passive"))
    )
    (net (code "154") (name "unconnected-(U18A-T3-PadA41)") (class "Default")
      (node (ref "U18") (pin "A41") (pinfunction "T3_A41") (pintype "passive"))
    )
    (net (code "155") (name "unconnected-(U18A-T4-PadA43)") (class "Default")
      (node (ref "U18") (pin "A43") (pinfunction "T4_A43") (pintype "passive"))
    )
    (net (code "156") (name "unconnected-(U18A-TDO-App_TDI-PadA72)") (class "Default")
      (node (ref "U18") (pin "A72") (pinfunction "TDO-App_TDI_A72") (pintype "passive"))
    )
    (net (code "157") (name "unconnected-(U18B-Direction4-PadB45)") (class "Default")
      (node (ref "U18") (pin "B45") (pinfunction "Direction4_B45") (pintype "passive"))
    )
    (net (code "158") (name "unconnected-(U18B-GP_Out_D5-PadB14)") (class "Default")
      (node (ref "U18") (pin "B14") (pinfunction "GP_Out_D5_B14") (pintype "passive"))
    )
    (net (code "159") (name "unconnected-(U18B-GP_Out_D6-PadB18)") (class "Default")
      (node (ref "U18") (pin "B18") (pinfunction "GP_Out_D6_B18") (pintype "passive"))
    )
    (net (code "160") (name "unconnected-(U18B-GP_Out_D7-PadB22)") (class "Default")
      (node (ref "U18") (pin "B22") (pinfunction "GP_Out_D7_B22") (pintype "passive"))
    )
    (net (code "161") (name "unconnected-(U18B-GP_Out_D8-PadB26)") (class "Default")
      (node (ref "U18") (pin "B26") (pinfunction "GP_Out_D8_B26") (pintype "passive"))
    )
    (net (code "162") (name "unconnected-(U18B-GP_Out_D9-PadB30)") (class "Default")
      (node (ref "U18") (pin "B30") (pinfunction "GP_Out_D9_B30") (pintype "passive"))
    )
    (net (code "163") (name "unconnected-(U18B-GP_Out_D10-PadB34)") (class "Default")
      (node (ref "U18") (pin "B34") (pinfunction "GP_Out_D10_B34") (pintype "passive"))
    )
    (net (code "164") (name "unconnected-(U18B-GP_Out_D11-PadB38)") (class "Default")
      (node (ref "U18") (pin "B38") (pinfunction "GP_Out_D11_B38") (pintype "passive"))
    )
    (net (code "165") (name "unconnected-(U18B-GP_Out_D12-PadB42)") (class "Default")
      (node (ref "U18") (pin "B42") (pinfunction "GP_Out_D12_B42") (pintype "passive"))
    )
    (net (code "166") (name "unconnected-(U18B-GP_Out_D13-PadB46)") (class "Default")
      (node (ref "U18") (pin "B46") (pinfunction "GP_Out_D13_B46") (pintype "passive"))
    )
    (net (code "167") (name "unconnected-(U18B-GP_Out_D14-PadB50)") (class "Default")
      (node (ref "U18") (pin "B50") (pinfunction "GP_Out_D14_B50") (pintype "passive"))
    )
    (net (code "168") (name "unconnected-(U18B-GP_Out_D15-PadB54)") (class "Default")
      (node (ref "U18") (pin "B54") (pinfunction "GP_Out_D15_B54") (pintype "passive"))
    )
    (net (code "169") (name "unconnected-(U18B-GP_Out_D16-PadB58)") (class "Default")
      (node (ref "U18") (pin "B58") (pinfunction "GP_Out_D16_B58") (pintype "passive"))
    )
    (net (code "170") (name "unconnected-(U18B-GP_Out_D17-PadB62)") (class "Default")
      (node (ref "U18") (pin "B62") (pinfunction "GP_Out_D17_B62") (pintype "passive"))
    )
    (net (code "171") (name "unconnected-(U18B-GP_Out_D18-PadB66)") (class "Default")
      (node (ref "U18") (pin "B66") (pinfunction "GP_Out_D18_B66") (pintype "passive"))
    )
    (net (code "172") (name "unconnected-(U18B-GP_Out_D19-PadB70)") (class "Default")
      (node (ref "U18") (pin "B70") (pinfunction "GP_Out_D19_B70") (pintype "passive"))
    )
    (net (code "173") (name "unconnected-(U18B-GP_Out_D20-PadB74)") (class "Default")
      (node (ref "U18") (pin "B74") (pinfunction "GP_Out_D20_B74") (pintype "passive"))
    )
    (net (code "174") (name "unconnected-(U18B-GP_Out_D21-PadB78)") (class "Default")
      (node (ref "U18") (pin "B78") (pinfunction "GP_Out_D21_B78") (pintype "passive"))
    )
    (net (code "175") (name "unconnected-(U18B-GP_Out_D22-PadB82)") (class "Default")
      (node (ref "U18") (pin "B82") (pinfunction "GP_Out_D22_B82") (pintype "passive"))
    )
    (net (code "176") (name "unconnected-(U18B-GP_Out_D23-PadB86)") (class "Default")
      (node (ref "U18") (pin "B86") (pinfunction "GP_Out_D23_B86") (pintype "passive"))
    )
    (net (code "177") (name "unconnected-(U18B-GP_Out_D24-PadB90)") (class "Default")
      (node (ref "U18") (pin "B90") (pinfunction "GP_Out_D24_B90") (pintype "passive"))
    )
    (net (code "178") (name "unconnected-(U18B-GP_Out_D25-PadB94)") (class "Default")
      (node (ref "U18") (pin "B94") (pinfunction "GP_Out_D25_B94") (pintype "passive"))
    )
    (net (code "179") (name "unconnected-(U18B-GP_Out_D26-PadB98)") (class "Default")
      (node (ref "U18") (pin "B98") (pinfunction "GP_Out_D26_B98") (pintype "passive"))
    )
    (net (code "180") (name "unconnected-(U18B-GP_Out_D27-PadB102)") (class "Default")
      (node (ref "U18") (pin "B102") (pinfunction "GP_Out_D27_B102") (pintype "passive"))
    )
    (net (code "181") (name "unconnected-(U18B-GP_Out_D28-PadB106)") (class "Default")
      (node (ref "U18") (pin "B106") (pinfunction "GP_Out_D28_B106") (pintype "passive"))
    )
    (net (code "182") (name "unconnected-(U18B-GP_Out_D29-PadB110)") (class "Default")
      (node (ref "U18") (pin "B110") (pinfunction "GP_Out_D29_B110") (pintype "passive"))
    )
    (net (code "183") (name "unconnected-(U18B-GP_Out_D30-PadB114)") (class "Default")
      (node (ref "U18") (pin "B114") (pinfunction "GP_Out_D30_B114") (pintype "passive"))
    )
    (net (code "184") (name "unconnected-(U18B-GP_Out_D31-PadB118)") (class "Default")
      (node (ref "U18") (pin "B118") (pinfunction "GP_Out_D31_B118") (pintype "passive"))
    )
    (net (code "185") (name "unconnected-(U18B-GP_Out_S5-PadB16)") (class "Default")
      (node (ref "U18") (pin "B16") (pinfunction "GP_Out_S5_B16") (pintype "passive"))
    )
    (net (code "186") (name "unconnected-(U18B-GP_Out_S6-PadB20)") (class "Default")
      (node (ref "U18") (pin "B20") (pinfunction "GP_Out_S6_B20") (pintype "passive"))
    )
    (net (code "187") (name "unconnected-(U18B-GP_Out_S7-PadB24)") (class "Default")
      (node (ref "U18") (pin "B24") (pinfunction "GP_Out_S7_B24") (pintype "passive"))
    )
    (net (code "188") (name "unconnected-(U18B-GP_Out_S8-PadB28)") (class "Default")
      (node (ref "U18") (pin "B28") (pinfunction "GP_Out_S8_B28") (pintype "passive"))
    )
    (net (code "189") (name "unconnected-(U18B-GP_Out_S9-PadB32)") (class "Default")
      (node (ref "U18") (pin "B32") (pinfunction "GP_Out_S9_B32") (pintype "passive"))
    )
    (net (code "190") (name "unconnected-(U18B-GP_Out_S10-PadB36)") (class "Default")
      (node (ref "U18") (pin "B36") (pinfunction "GP_Out_S10_B36") (pintype "passive"))
    )
    (net (code "191") (name "unconnected-(U18B-GP_Out_S11-PadB40)") (class "Default")
      (node (ref "U18") (pin "B40") (pinfunction "GP_Out_S11_B40") (pintype "passive"))
    )
    (net (code "192") (name "unconnected-(U18B-GP_Out_S12-PadB44)") (class "Default")
      (node (ref "U18") (pin "B44") (pinfunction "GP_Out_S12_B44") (pintype "passive"))
    )
    (net (code "193") (name "unconnected-(U18B-GP_Out_S13-PadB48)") (class "Default")
      (node (ref "U18") (pin "B48") (pinfunction "GP_Out_S13_B48") (pintype "passive"))
    )
    (net (code "194") (name "unconnected-(U18B-GP_Out_S14-PadB52)") (class "Default")
      (node (ref "U18") (pin "B52") (pinfunction "GP_Out_S14_B52") (pintype "passive"))
    )
    (net (code "195") (name "unconnected-(U18B-GP_Out_S15-PadB56)") (class "Default")
      (node (ref "U18") (pin "B56") (pinfunction "GP_Out_S15_B56") (pintype "passive"))
    )
    (net (code "196") (name "unconnected-(U18B-GP_Out_S16-PadB60)") (class "Default")
      (node (ref "U18") (pin "B60") (pinfunction "GP_Out_S16_B60") (pintype "passive"))
    )
    (net (code "197") (name "unconnected-(U18B-GP_Out_S17-PadB64)") (class "Default")
      (node (ref "U18") (pin "B64") (pinfunction "GP_Out_S17_B64") (pintype "passive"))
    )
    (net (code "198") (name "unconnected-(U18B-GP_Out_S18-PadB68)") (class "Default")
      (node (ref "U18") (pin "B68") (pinfunction "GP_Out_S18_B68") (pintype "passive"))
    )
    (net (code "199") (name "unconnected-(U18B-GP_Out_S19-PadB72)") (class "Default")
      (node (ref "U18") (pin "B72") (pinfunction "GP_Out_S19_B72") (pintype "passive"))
    )
    (net (code "200") (name "unconnected-(U18B-GP_Out_S20-PadB76)") (class "Default")
      (node (ref "U18") (pin "B76") (pinfunction "GP_Out_S20_B76") (pintype "passive"))
    )
    (net (code "201") (name "unconnected-(U18B-GP_Out_S21-PadB80)") (class "Default")
      (node (ref "U18") (pin "B80") (pinfunction "GP_Out_S21_B80") (pintype "passive"))
    )
    (net (code "202") (name "unconnected-(U18B-GP_Out_S22-PadB84)") (class "Default")
      (node (ref "U18") (pin "B84") (pinfunction "GP_Out_S22_B84") (pintype "passive"))
    )
    (net (code "203") (name "unconnected-(U18B-GP_Out_S23-PadB88)") (class "Default")
      (node (ref "U18") (pin "B88") (pinfunction "GP_Out_S23_B88") (pintype "passive"))
    )
    (net (code "204") (name "unconnected-(U18B-GP_Out_S24-PadB92)") (class "Default")
      (node (ref "U18") (pin "B92") (pinfunction "GP_Out_S24_B92") (pintype "passive"))
    )
    (net (code "205") (name "unconnected-(U18B-GP_Out_S25-PadB96)") (class "Default")
      (node (ref "U18") (pin "B96") (pinfunction "GP_Out_S25_B96") (pintype "passive"))
    )
    (net (code "206") (name "unconnected-(U18B-GP_Out_S26-PadB100)") (class "Default")
      (node (ref "U18") (pin "B100") (pinfunction "GP_Out_S26_B100") (pintype "passive"))
    )
    (net (code "207") (name "unconnected-(U18B-GP_Out_S27-PadB104)") (class "Default")
      (node (ref "U18") (pin "B104") (pinfunction "GP_Out_S27_B104") (pintype "passive"))
    )
    (net (code "208") (name "unconnected-(U18B-GP_Out_S28-PadB108)") (class "Default")
      (node (ref "U18") (pin "B108") (pinfunction "GP_Out_S28_B108") (pintype "passive"))
    )
    (net (code "209") (name "unconnected-(U18B-GP_Out_S29-PadB112)") (class "Default")
      (node (ref "U18") (pin "B112") (pinfunction "GP_Out_S29_B112") (pintype "passive"))
    )
    (net (code "210") (name "unconnected-(U18B-GP_Out_S30-PadB116)") (class "Default")
      (node (ref "U18") (pin "B116") (pinfunction "GP_Out_S30_B116") (pintype "passive"))
    )
    (net (code "211") (name "unconnected-(U18B-GP_Out_S31-PadB120)") (class "Default")
      (node (ref "U18") (pin "B120") (pinfunction "GP_Out_S31_B120") (pintype "passive"))
    )
    (net (code "212") (name "unconnected-(U18B-HomeCom-PadB9)") (class "Default")
      (node (ref "U18") (pin "B9") (pinfunction "HomeCom_B9") (pintype "passive"))
    )
    (net (code "213") (name "unconnected-(U18B-NegLimt4-PadB21)") (class "Default")
      (node (ref "U18") (pin "B21") (pinfunction "NegLimt4_B21") (pintype "passive"))
    )
    (net (code "214") (name "unconnected-(U18B-Opto_Input1-PadB59)") (class "Default")
      (node (ref "U18") (pin "B59") (pinfunction "Opto_Input1_B59") (pintype "passive"))
    )
    (net (code "215") (name "unconnected-(U18B-Opto_Input2-PadB61)") (class "Default")
      (node (ref "U18") (pin "B61") (pinfunction "Opto_Input2_B61") (pintype "passive"))
    )
    (net (code "216") (name "unconnected-(U18B-Opto_Input3-PadB63)") (class "Default")
      (node (ref "U18") (pin "B63") (pinfunction "Opto_Input3_B63") (pintype "passive"))
    )
    (net (code "217") (name "unconnected-(U18B-Opto_Input4-PadB73)") (class "Default")
      (node (ref "U18") (pin "B73") (pinfunction "Opto_Input4_B73") (pintype "passive"))
    )
    (net (code "218") (name "unconnected-(U18B-Opto_Input5-PadB75)") (class "Default")
      (node (ref "U18") (pin "B75") (pinfunction "Opto_Input5_B75") (pintype "passive"))
    )
    (net (code "219") (name "unconnected-(U18B-Opto_Input6-PadB77)") (class "Default")
      (node (ref "U18") (pin "B77") (pinfunction "Opto_Input6_B77") (pintype "passive"))
    )
    (net (code "220") (name "unconnected-(U18B-Opto_Input7-PadB79)") (class "Default")
      (node (ref "U18") (pin "B79") (pinfunction "Opto_Input7_B79") (pintype "passive"))
    )
    (net (code "221") (name "unconnected-(U18B-Opto_Input8-PadB83)") (class "Default")
      (node (ref "U18") (pin "B83") (pinfunction "Opto_Input8_B83") (pintype "passive"))
    )
    (net (code "222") (name "unconnected-(U18B-Opto_Input9-PadB85)") (class "Default")
      (node (ref "U18") (pin "B85") (pinfunction "Opto_Input9_B85") (pintype "passive"))
    )
    (net (code "223") (name "unconnected-(U18B-Opto_Input10-PadB87)") (class "Default")
      (node (ref "U18") (pin "B87") (pinfunction "Opto_Input10_B87") (pintype "passive"))
    )
    (net (code "224") (name "unconnected-(U18B-Opto_Input11-PadB89)") (class "Default")
      (node (ref "U18") (pin "B89") (pinfunction "Opto_Input11_B89") (pintype "passive"))
    )
    (net (code "225") (name "unconnected-(U18B-Opto_Input12-PadB93)") (class "Default")
      (node (ref "U18") (pin "B93") (pinfunction "Opto_Input12_B93") (pintype "passive"))
    )
    (net (code "226") (name "unconnected-(U18B-Opto_Input13-PadB95)") (class "Default")
      (node (ref "U18") (pin "B95") (pinfunction "Opto_Input13_B95") (pintype "passive"))
    )
    (net (code "227") (name "unconnected-(U18B-Opto_Input14-PadB97)") (class "Default")
      (node (ref "U18") (pin "B97") (pinfunction "Opto_Input14_B97") (pintype "passive"))
    )
    (net (code "228") (name "unconnected-(U18B-Opto_Input15-PadB99)") (class "Default")
      (node (ref "U18") (pin "B99") (pinfunction "Opto_Input15_B99") (pintype "passive"))
    )
    (net (code "229") (name "unconnected-(U18B-Opto_Input16-PadB103)") (class "Default")
      (node (ref "U18") (pin "B103") (pinfunction "Opto_Input16_B103") (pintype "passive"))
    )
    (net (code "230") (name "unconnected-(U18B-Opto_Input17-PadB105)") (class "Default")
      (node (ref "U18") (pin "B105") (pinfunction "Opto_Input17_B105") (pintype "passive"))
    )
    (net (code "231") (name "unconnected-(U18B-Opto_Input18-PadB107)") (class "Default")
      (node (ref "U18") (pin "B107") (pinfunction "Opto_Input18_B107") (pintype "passive"))
    )
    (net (code "232") (name "unconnected-(U18B-Opto_Input19-PadB109)") (class "Default")
      (node (ref "U18") (pin "B109") (pinfunction "Opto_Input19_B109") (pintype "passive"))
    )
    (net (code "233") (name "unconnected-(U18B-Opto_Input20-PadB113)") (class "Default")
      (node (ref "U18") (pin "B113") (pinfunction "Opto_Input20_B113") (pintype "passive"))
    )
    (net (code "234") (name "unconnected-(U18B-Opto_Input21-PadB115)") (class "Default")
      (node (ref "U18") (pin "B115") (pinfunction "Opto_Input21_B115") (pintype "passive"))
    )
    (net (code "235") (name "unconnected-(U18B-Opto_Input22-PadB117)") (class "Default")
      (node (ref "U18") (pin "B117") (pinfunction "Opto_Input22_B117") (pintype "passive"))
    )
    (net (code "236") (name "unconnected-(U18B-Opto_Input23-PadB119)") (class "Default")
      (node (ref "U18") (pin "B119") (pinfunction "Opto_Input23_B119") (pintype "passive"))
    )
    (net (code "237") (name "unconnected-(U18B-Opto_Input_Com1-PadB71)") (class "Default")
      (node (ref "U18") (pin "B71") (pinfunction "Opto_Input_Com1_B71") (pintype "passive"))
    )
    (net (code "238") (name "unconnected-(U18B-Opto_Input_Com2-PadB81)") (class "Default")
      (node (ref "U18") (pin "B81") (pinfunction "Opto_Input_Com2_B81") (pintype "passive"))
    )
    (net (code "239") (name "unconnected-(U18B-Opto_Input_Com3-PadB91)") (class "Default")
      (node (ref "U18") (pin "B91") (pinfunction "Opto_Input_Com3_B91") (pintype "passive"))
    )
    (net (code "240") (name "unconnected-(U18B-Opto_Input_Com4-PadB101)") (class "Default")
      (node (ref "U18") (pin "B101") (pinfunction "Opto_Input_Com4_B101") (pintype "passive"))
    )
    (net (code "241") (name "unconnected-(U18B-Opto_Input_Com5-PadB111)") (class "Default")
      (node (ref "U18") (pin "B111") (pinfunction "Opto_Input_Com5_B111") (pintype "passive"))
    )
    (net (code "242") (name "unconnected-(U18B-PosLimt4-PadB11)") (class "Default")
      (node (ref "U18") (pin "B11") (pinfunction "PosLimt4_B11") (pintype "passive"))
    )
    (net (code "243") (name "unconnected-(U18B-Step4-PadB37)") (class "Default")
      (node (ref "U18") (pin "B37") (pinfunction "Step4_B37") (pintype "passive"))
    )
    (net (code "244") (name "unconnected-(U18B-~Home1-PadB7)") (class "Default")
      (node (ref "U18") (pin "B7") (pinfunction "~Home1_B7") (pintype "passive"))
    )
    (net (code "245") (name "unconnected-(U18B-~Home2-PadB5)") (class "Default")
      (node (ref "U18") (pin "B5") (pinfunction "~Home2_B5") (pintype "passive"))
    )
    (net (code "246") (name "unconnected-(U18B-~Home3-PadB3)") (class "Default")
      (node (ref "U18") (pin "B3") (pinfunction "~Home3_B3") (pintype "passive"))
    )
    (net (code "247") (name "unconnected-(U18B-~Home4-PadB1)") (class "Default")
      (node (ref "U18") (pin "B1") (pinfunction "~Home4_B1") (pintype "passive"))
    )
  )
)
